# OwlPedal.net
KiCad netlist of a schematic drawn in EAGLE
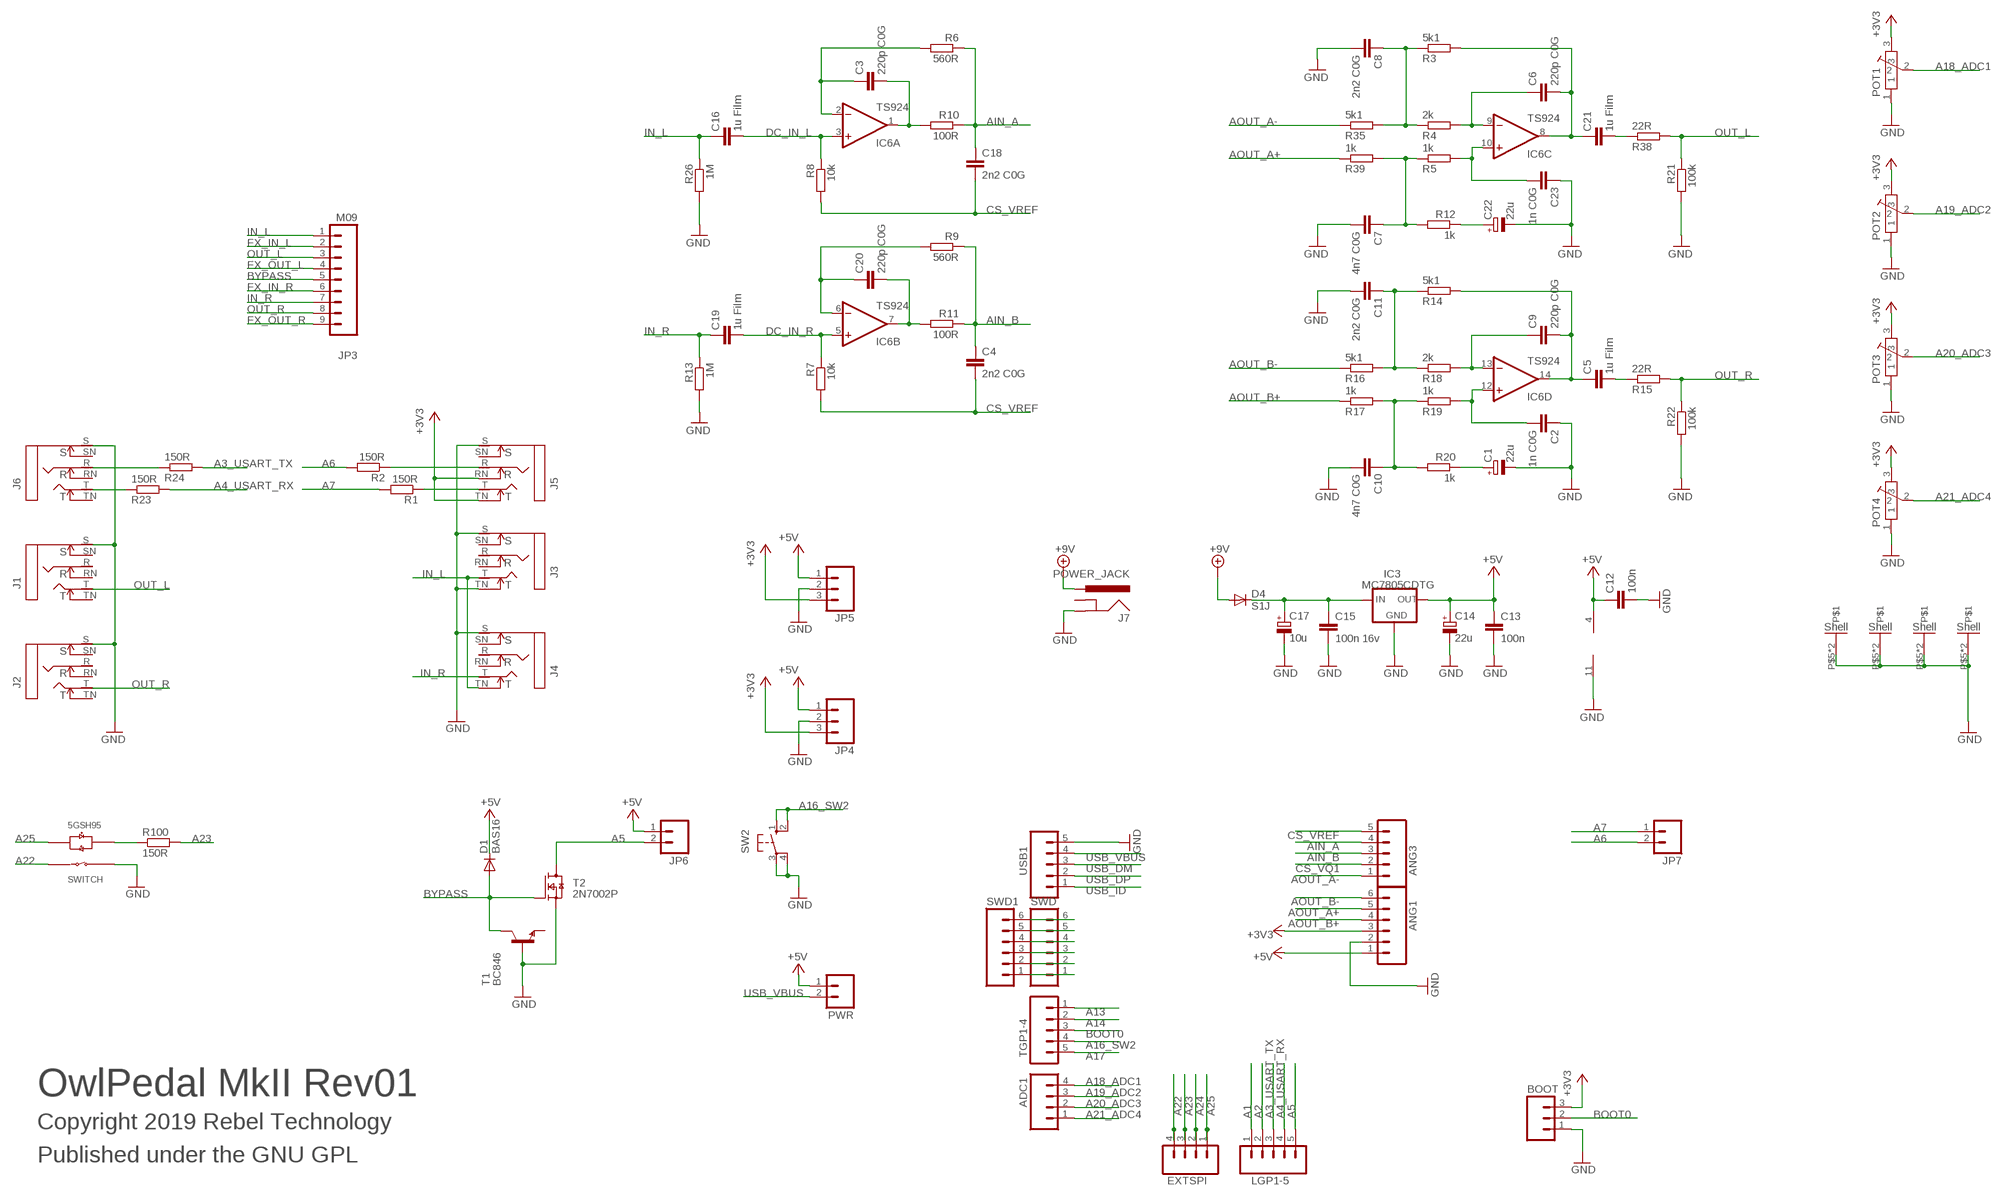
[diagram p0: schematic, sheet 1]

(export (version "E")
  (design (tool "Eeschema 10.0.6"))
  (components
    (comp (ref "ADC1")
      (value "M04PTH")
      (footprint "eagle-import:1X04")
      (libsource (lib "eagle-import") (part "M04PTH"))
    )
    (comp (ref "ANG1")
      (value "M06SIP")
      (footprint "eagle-import:1X06")
      (libsource (lib "eagle-import") (part "M06SIP"))
    )
    (comp (ref "ANG3")
      (value "M05PTH")
      (footprint "eagle-import:1X05")
      (libsource (lib "eagle-import") (part "M05PTH"))
    )
    (comp (ref "BOOT")
      (value "M03PTH")
      (footprint "eagle-import:1X03")
      (libsource (lib "eagle-import") (part "M03PTH"))
    )
    (comp (ref "C1")
      (value "22u")
      (footprint "eagle-import:CPOL-5")
      (libsource (lib "eagle-import") (part "CPOL-EU153CLV-0505"))
    )
    (comp (ref "C2")
      (value "1n C0G")
      (footprint "eagle-import:C0603")
      (libsource (lib "eagle-import") (part "resistor_C-EUC0603"))
    )
    (comp (ref "C3")
      (value "220p C0G")
      (footprint "eagle-import:C0603")
      (libsource (lib "eagle-import") (part "resistor_C-EUC0603"))
    )
    (comp (ref "C4")
      (value "2n2 C0G")
      (footprint "eagle-import:C0603")
      (libsource (lib "eagle-import") (part "resistor_C-EUC0603"))
    )
    (comp (ref "C5")
      (value "1u Film")
      (footprint "eagle-import:C1210")
      (libsource (lib "eagle-import") (part "C-EUC1210"))
    )
    (comp (ref "C6")
      (value "220p C0G")
      (footprint "eagle-import:C0603")
      (libsource (lib "eagle-import") (part "resistor_C-EUC0603"))
    )
    (comp (ref "C7")
      (value "4n7 C0G")
      (footprint "eagle-import:C0603")
      (libsource (lib "eagle-import") (part "resistor_C-EUC0603"))
    )
    (comp (ref "C8")
      (value "2n2 C0G")
      (footprint "eagle-import:C0603")
      (libsource (lib "eagle-import") (part "resistor_C-EUC0603"))
    )
    (comp (ref "C9")
      (value "220p C0G")
      (footprint "eagle-import:C0603")
      (libsource (lib "eagle-import") (part "resistor_C-EUC0603"))
    )
    (comp (ref "C10")
      (value "4n7 C0G")
      (footprint "eagle-import:C0603")
      (libsource (lib "eagle-import") (part "resistor_C-EUC0603"))
    )
    (comp (ref "C11")
      (value "2n2 C0G")
      (footprint "eagle-import:C0603")
      (libsource (lib "eagle-import") (part "resistor_C-EUC0603"))
    )
    (comp (ref "C12")
      (value "100n")
      (footprint "eagle-import:C0603")
      (libsource (lib "eagle-import") (part "resistor_C-EUC0603"))
    )
    (comp (ref "C13")
      (value "100n")
      (footprint "eagle-import:C0603")
      (libsource (lib "eagle-import") (part "C-EUC0603"))
    )
    (comp (ref "C14")
      (value "22u")
      (footprint "eagle-import:CPOL-5")
      (libsource (lib "eagle-import") (part "CPOL-EU153CLV-0505"))
    )
    (comp (ref "C15")
      (value "100n 16v")
      (footprint "eagle-import:C0603")
      (libsource (lib "eagle-import") (part "C-EUC0603"))
    )
    (comp (ref "C16")
      (value "1u Film")
      (footprint "eagle-import:C1210")
      (libsource (lib "eagle-import") (part "C-EUC1210"))
    )
    (comp (ref "C17")
      (value "10u")
      (footprint "eagle-import:CPOL-5")
      (libsource (lib "eagle-import") (part "CPOL-EU153CLV-0505"))
    )
    (comp (ref "C18")
      (value "2n2 C0G")
      (footprint "eagle-import:C0603")
      (libsource (lib "eagle-import") (part "resistor_C-EUC0603"))
    )
    (comp (ref "C19")
      (value "1u Film")
      (footprint "eagle-import:C1210")
      (libsource (lib "eagle-import") (part "C-EUC1210"))
    )
    (comp (ref "C20")
      (value "220p C0G")
      (footprint "eagle-import:C0603")
      (libsource (lib "eagle-import") (part "resistor_C-EUC0603"))
    )
    (comp (ref "C21")
      (value "1u Film")
      (footprint "eagle-import:C1210")
      (libsource (lib "eagle-import") (part "C-EUC1210"))
    )
    (comp (ref "C22")
      (value "22u")
      (footprint "eagle-import:CPOL-5")
      (libsource (lib "eagle-import") (part "CPOL-EU153CLV-0505"))
    )
    (comp (ref "C23")
      (value "1n C0G")
      (footprint "eagle-import:C0603")
      (libsource (lib "eagle-import") (part "resistor_C-EUC0603"))
    )
    (comp (ref "D1")
      (value "BAS16")
      (footprint "eagle-import:SOT23")
      (libsource (lib "eagle-import") (part "BAS16"))
    )
    (comp (ref "D4")
      (value "S1J")
      (footprint "eagle-import:SMA-DIODE")
      (libsource (lib "eagle-import") (part "DIODESMA"))
    )
    (comp (ref "EXTSPI")
      (value "M04PTH")
      (footprint "eagle-import:1X04")
      (libsource (lib "eagle-import") (part "M04PTH"))
    )
    (comp (ref "IC3")
      (value "MC7805CDTG")
      (footprint "eagle-import:DPACK")
      (libsource (lib "eagle-import") (part "MC78XX"))
    )
    (comp (ref "IC6")
      (value "TS924")
      (footprint "eagle-import:SO14")
      (libsource (lib "eagle-import") (part "LM324D"))
    )
    (comp (ref "J1")
      (value "NEUTRIK_NMJ6HCD2")
      (footprint "eagle-import:NMJ6HCD2")
      (libsource (lib "eagle-import") (part "NEUTRIK_NMJ6HCD2"))
    )
    (comp (ref "J2")
      (value "NEUTRIK_NMJ6HCD2")
      (footprint "eagle-import:NMJ6HCD2")
      (libsource (lib "eagle-import") (part "NEUTRIK_NMJ6HCD2"))
    )
    (comp (ref "J3")
      (value "NEUTRIK_NMJ6HCD2")
      (footprint "eagle-import:NMJ6HCD2")
      (libsource (lib "eagle-import") (part "NEUTRIK_NMJ6HCD2"))
    )
    (comp (ref "J4")
      (value "NEUTRIK_NMJ6HCD2")
      (footprint "eagle-import:NMJ6HCD2")
      (libsource (lib "eagle-import") (part "NEUTRIK_NMJ6HCD2"))
    )
    (comp (ref "J5")
      (value "NEUTRIK_NMJ6HCD2")
      (footprint "eagle-import:NMJ6HCD2")
      (libsource (lib "eagle-import") (part "NEUTRIK_NMJ6HCD2"))
    )
    (comp (ref "J6")
      (value "NEUTRIK_NMJ6HCD2")
      (footprint "eagle-import:NMJ6HCD2")
      (libsource (lib "eagle-import") (part "NEUTRIK_NMJ6HCD2"))
    )
    (comp (ref "J7")
      (value "POWER_JACK")
      (footprint "eagle-import:DC_JACK_SLOT")
      (libsource (lib "eagle-import") (part "POWER_JACK"))
    )
    (comp (ref "JP3")
      (value "M09")
      (footprint "eagle-import:1X09")
      (libsource (lib "eagle-import") (part "M09"))
    )
    (comp (ref "JP4")
      (value "M03PTH")
      (footprint "eagle-import:1X03")
      (libsource (lib "eagle-import") (part "M03PTH"))
    )
    (comp (ref "JP5")
      (value "M03PTH")
      (footprint "eagle-import:1X03")
      (libsource (lib "eagle-import") (part "M03PTH"))
    )
    (comp (ref "JP6")
      (value "M02PTH")
      (footprint "eagle-import:1X02")
      (libsource (lib "eagle-import") (part "M02PTH"))
    )
    (comp (ref "JP7")
      (value "M02PTH")
      (footprint "eagle-import:1X02")
      (libsource (lib "eagle-import") (part "M02PTH"))
    )
    (comp (ref "LGP1-5")
      (value "M05PTH")
      (footprint "eagle-import:1X05")
      (libsource (lib "eagle-import") (part "M05PTH"))
    )
    (comp (ref "POT1")
      (value "POT-ALPS-RK09L1140")
      (footprint "eagle-import:POT-ALPS-RK09L1140")
      (libsource (lib "eagle-import") (part "POT-ALPS-RK09L1140"))
    )
    (comp (ref "POT2")
      (value "POT-ALPS-RK09L1140")
      (footprint "eagle-import:POT-ALPS-RK09L1140")
      (libsource (lib "eagle-import") (part "POT-ALPS-RK09L1140"))
    )
    (comp (ref "POT3")
      (value "POT-ALPS-RK09L1140")
      (footprint "eagle-import:POT-ALPS-RK09L1140")
      (libsource (lib "eagle-import") (part "POT-ALPS-RK09L1140"))
    )
    (comp (ref "POT4")
      (value "POT-ALPS-RK09L1140")
      (footprint "eagle-import:POT-ALPS-RK09L1140")
      (libsource (lib "eagle-import") (part "POT-ALPS-RK09L1140"))
    )
    (comp (ref "PWR")
      (value "M02PTH")
      (footprint "eagle-import:1X02")
      (libsource (lib "eagle-import") (part "M02PTH"))
    )
    (comp (ref "R1")
      (value "150R")
      (footprint "eagle-import:0603")
      (libsource (lib "eagle-import") (part "R-EU_0603"))
    )
    (comp (ref "R2")
      (value "150R")
      (footprint "eagle-import:0603")
      (libsource (lib "eagle-import") (part "R-EU_0603"))
    )
    (comp (ref "R3")
      (value "5k1")
      (footprint "eagle-import:0603")
      (libsource (lib "eagle-import") (part "R-EU_0603"))
    )
    (comp (ref "R4")
      (value "2k")
      (footprint "eagle-import:0603")
      (libsource (lib "eagle-import") (part "R-EU_0603"))
    )
    (comp (ref "R5")
      (value "1k")
      (footprint "eagle-import:0603")
      (libsource (lib "eagle-import") (part "R-EU_0603"))
    )
    (comp (ref "R6")
      (value "560R")
      (footprint "eagle-import:0603")
      (libsource (lib "eagle-import") (part "R-EU_0603"))
    )
    (comp (ref "R7")
      (value "10k")
      (footprint "eagle-import:0603")
      (libsource (lib "eagle-import") (part "R-EU_0603"))
    )
    (comp (ref "R8")
      (value "10k")
      (footprint "eagle-import:0603")
      (libsource (lib "eagle-import") (part "R-EU_0603"))
    )
    (comp (ref "R9")
      (value "560R")
      (footprint "eagle-import:0603")
      (libsource (lib "eagle-import") (part "R-EU_0603"))
    )
    (comp (ref "R10")
      (value "100R")
      (footprint "eagle-import:0603")
      (libsource (lib "eagle-import") (part "R-EU_0603"))
    )
    (comp (ref "R11")
      (value "100R")
      (footprint "eagle-import:0603")
      (libsource (lib "eagle-import") (part "R-EU_0603"))
    )
    (comp (ref "R12")
      (value "1k")
      (footprint "eagle-import:0603")
      (libsource (lib "eagle-import") (part "R-EU_0603"))
    )
    (comp (ref "R13")
      (value "1M")
      (footprint "eagle-import:0603")
      (libsource (lib "eagle-import") (part "R-EU_0603"))
    )
    (comp (ref "R14")
      (value "5k1")
      (footprint "eagle-import:0603")
      (libsource (lib "eagle-import") (part "R-EU_0603"))
    )
    (comp (ref "R15")
      (value "22R")
      (footprint "eagle-import:0603")
      (libsource (lib "eagle-import") (part "R-EU_0603"))
    )
    (comp (ref "R16")
      (value "5k1")
      (footprint "eagle-import:0603")
      (libsource (lib "eagle-import") (part "R-EU_0603"))
    )
    (comp (ref "R17")
      (value "1k")
      (footprint "eagle-import:0603")
      (libsource (lib "eagle-import") (part "R-EU_0603"))
    )
    (comp (ref "R18")
      (value "2k")
      (footprint "eagle-import:0603")
      (libsource (lib "eagle-import") (part "R-EU_0603"))
    )
    (comp (ref "R19")
      (value "1k")
      (footprint "eagle-import:0603")
      (libsource (lib "eagle-import") (part "R-EU_0603"))
    )
    (comp (ref "R20")
      (value "1k")
      (footprint "eagle-import:0603")
      (libsource (lib "eagle-import") (part "R-EU_0603"))
    )
    (comp (ref "R21")
      (value "100k")
      (footprint "eagle-import:0603")
      (libsource (lib "eagle-import") (part "R-EU_0603"))
    )
    (comp (ref "R22")
      (value "100k")
      (footprint "eagle-import:0603")
      (libsource (lib "eagle-import") (part "R-EU_0603"))
    )
    (comp (ref "R23")
      (value "150R")
      (footprint "eagle-import:0603")
      (libsource (lib "eagle-import") (part "R-EU_0603"))
    )
    (comp (ref "R24")
      (value "150R")
      (footprint "eagle-import:0603")
      (libsource (lib "eagle-import") (part "R-EU_0603"))
    )
    (comp (ref "R26")
      (value "1M")
      (footprint "eagle-import:0603")
      (libsource (lib "eagle-import") (part "R-EU_0603"))
    )
    (comp (ref "R35")
      (value "5k1")
      (footprint "eagle-import:0603")
      (libsource (lib "eagle-import") (part "R-EU_0603"))
    )
    (comp (ref "R38")
      (value "22R")
      (footprint "eagle-import:0603")
      (libsource (lib "eagle-import") (part "R-EU_0603"))
    )
    (comp (ref "R39")
      (value "1k")
      (footprint "eagle-import:0603")
      (libsource (lib "eagle-import") (part "R-EU_0603"))
    )
    (comp (ref "R100")
      (value "150R")
      (footprint "eagle-import:0603")
      (libsource (lib "eagle-import") (part "R-EU_0603"))
    )
    (comp (ref "SW2")
      (value "10-XX")
      (footprint "eagle-import:B3F-10XX")
      (fields (field (name "MPN") "B3F-1000"))
      (libsource (lib "eagle-import") (part "10-XX"))
    )
    (comp (ref "SWD")
      (value "M06SIP")
      (footprint "eagle-import:1X06")
      (libsource (lib "eagle-import") (part "M06SIP"))
    )
    (comp (ref "SWD1")
      (value "M06SIP")
      (footprint "eagle-import:1X06")
      (libsource (lib "eagle-import") (part "M06SIP"))
    )
    (comp (ref "T1")
      (value "BC846")
      (footprint "eagle-import:SOT23")
      (libsource (lib "eagle-import") (part "BC846"))
    )
    (comp (ref "T2")
      (value "2N7002P")
      (footprint "eagle-import:SOT23")
      (libsource (lib "eagle-import") (part "2N7002P"))
    )
    (comp (ref "TGP1-4")
      (value "M05PTH")
      (footprint "eagle-import:1X05")
      (libsource (lib "eagle-import") (part "M05PTH"))
    )
    (comp (ref "U$1")
      (value "5GTH9")
      (footprint "eagle-import:5GTH9")
      (libsource (lib "eagle-import") (part "5GTH9"))
    )
    (comp (ref "USB1")
      (value "M05PTH")
      (footprint "eagle-import:1X05")
      (libsource (lib "eagle-import") (part "M05PTH"))
    )
  )
  (nets
    (net (code "1") (name "+3V3") (class "Default")
      (node (ref "ANG1") (pin "3") (pinfunction "3_3") (pintype "passive"))
      (node (ref "BOOT") (pin "3") (pinfunction "3_3") (pintype "passive"))
      (node (ref "J5") (pin "RN") (pinfunction "RN_RN") (pintype "passive"))
      (node (ref "J5") (pin "TN") (pinfunction "TN_TN") (pintype "passive"))
      (node (ref "JP4") (pin "3") (pinfunction "3_3") (pintype "passive"))
      (node (ref "JP5") (pin "3") (pinfunction "3_3") (pintype "passive"))
      (node (ref "POT1") (pin "3") (pinfunction "3_3") (pintype "bidirectional"))
      (node (ref "POT2") (pin "3") (pinfunction "3_3") (pintype "bidirectional"))
      (node (ref "POT3") (pin "3") (pinfunction "3_3") (pintype "bidirectional"))
      (node (ref "POT4") (pin "3") (pinfunction "3_3") (pintype "bidirectional"))
    )
    (net (code "2") (name "+5V") (class "Default")
      (node (ref "ANG1") (pin "1") (pinfunction "1_1") (pintype "passive"))
      (node (ref "C12") (pin "1") (pinfunction "1_1") (pintype "passive"))
      (node (ref "C13") (pin "1") (pinfunction "1_1") (pintype "passive"))
      (node (ref "C14") (pin "+") (pinfunction "+_+") (pintype "passive"))
      (node (ref "D1") (pin "3") (pinfunction "K_3") (pintype "passive"))
      (node (ref "IC3") (pin "3") (pinfunction "OUT_3") (pintype "passive"))
      (node (ref "IC6") (pin "4") (pinfunction "V+_4") (pintype "power_in"))
      (node (ref "JP4") (pin "1") (pinfunction "1_1") (pintype "passive"))
      (node (ref "JP5") (pin "1") (pinfunction "1_1") (pintype "passive"))
      (node (ref "JP6") (pin "1") (pinfunction "1_1") (pintype "passive"))
      (node (ref "PWR") (pin "1") (pinfunction "1_1") (pintype "passive"))
    )
    (net (code "3") (name "+9V") (class "Default")
      (node (ref "D4") (pin "A") (pinfunction "A_A") (pintype "passive"))
      (node (ref "J7") (pin "PWR") (pinfunction "PWR_PWR") (pintype "bidirectional"))
    )
    (net (code "4") (name "/A1") (class "Default")
      (node (ref "LGP1-5") (pin "1") (pinfunction "1_1") (pintype "passive"))
    )
    (net (code "5") (name "/A2") (class "Default")
      (node (ref "LGP1-5") (pin "2") (pinfunction "2_2") (pintype "passive"))
    )
    (net (code "6") (name "/A3_USART_TX") (class "Default")
      (node (ref "LGP1-5") (pin "3") (pinfunction "3_3") (pintype "passive"))
      (node (ref "R24") (pin "2") (pinfunction "2_2") (pintype "passive"))
    )
    (net (code "7") (name "/A4_USART_RX") (class "Default")
      (node (ref "LGP1-5") (pin "4") (pinfunction "4_4") (pintype "passive"))
      (node (ref "R23") (pin "2") (pinfunction "2_2") (pintype "passive"))
    )
    (net (code "8") (name "/A5") (class "Default")
      (node (ref "JP6") (pin "2") (pinfunction "2_2") (pintype "passive"))
      (node (ref "LGP1-5") (pin "5") (pinfunction "5_5") (pintype "passive"))
      (node (ref "T2") (pin "3") (pinfunction "D_3") (pintype "passive"))
    )
    (net (code "9") (name "/A6") (class "Default")
      (node (ref "JP7") (pin "2") (pinfunction "2_2") (pintype "passive"))
      (node (ref "R2") (pin "2") (pinfunction "2_2") (pintype "passive"))
    )
    (net (code "10") (name "/A7") (class "Default")
      (node (ref "JP7") (pin "1") (pinfunction "1_1") (pintype "passive"))
      (node (ref "R1") (pin "2") (pinfunction "2_2") (pintype "passive"))
    )
    (net (code "11") (name "/A13") (class "Default")
      (node (ref "TGP1-4") (pin "1") (pinfunction "1_1") (pintype "passive"))
    )
    (net (code "12") (name "/A14") (class "Default")
      (node (ref "TGP1-4") (pin "2") (pinfunction "2_2") (pintype "passive"))
    )
    (net (code "13") (name "/A16_SW2") (class "Default")
      (node (ref "SW2") (pin "1") (pinfunction "S_1") (pintype "passive"))
      (node (ref "SW2") (pin "2") (pinfunction "S1_2") (pintype "passive"))
      (node (ref "TGP1-4") (pin "4") (pinfunction "4_4") (pintype "passive"))
    )
    (net (code "14") (name "/A17") (class "Default")
      (node (ref "TGP1-4") (pin "5") (pinfunction "5_5") (pintype "passive"))
    )
    (net (code "15") (name "/A18_ADC1") (class "Default")
      (node (ref "ADC1") (pin "4") (pinfunction "4_4") (pintype "passive"))
      (node (ref "POT1") (pin "2") (pinfunction "2_2") (pintype "bidirectional"))
    )
    (net (code "16") (name "/A19_ADC2") (class "Default")
      (node (ref "ADC1") (pin "3") (pinfunction "3_3") (pintype "passive"))
      (node (ref "POT2") (pin "2") (pinfunction "2_2") (pintype "bidirectional"))
    )
    (net (code "17") (name "/A20_ADC3") (class "Default")
      (node (ref "ADC1") (pin "2") (pinfunction "2_2") (pintype "passive"))
      (node (ref "POT3") (pin "2") (pinfunction "2_2") (pintype "bidirectional"))
    )
    (net (code "18") (name "/A21_ADC4") (class "Default")
      (node (ref "ADC1") (pin "1") (pinfunction "1_1") (pintype "passive"))
      (node (ref "POT4") (pin "2") (pinfunction "2_2") (pintype "bidirectional"))
    )
    (net (code "19") (name "/A22") (class "Default")
      (node (ref "EXTSPI") (pin "4") (pinfunction "4_4") (pintype "passive"))
      (node (ref "U$1") (pin "4") (pinfunction "SWITCH_A_4") (pintype "power_in"))
    )
    (net (code "20") (name "/A23") (class "Default")
      (node (ref "EXTSPI") (pin "3") (pinfunction "3_3") (pintype "passive"))
      (node (ref "R100") (pin "2") (pinfunction "2_2") (pintype "passive"))
    )
    (net (code "21") (name "/A24") (class "Default")
      (node (ref "EXTSPI") (pin "2") (pinfunction "2_2") (pintype "passive"))
    )
    (net (code "22") (name "/A25") (class "Default")
      (node (ref "EXTSPI") (pin "1") (pinfunction "1_1") (pintype "passive"))
      (node (ref "U$1") (pin "-2") (pinfunction "LED_G+_-2") (pintype "input"))
    )
    (net (code "23") (name "/AIN_A") (class "Default")
      (node (ref "ANG3") (pin "4") (pinfunction "4_4") (pintype "passive"))
      (node (ref "C18") (pin "1") (pinfunction "1_1") (pintype "passive"))
      (node (ref "R10") (pin "1") (pinfunction "1_1") (pintype "passive"))
      (node (ref "R6") (pin "1") (pinfunction "1_1") (pintype "passive"))
    )
    (net (code "24") (name "/AIN_B") (class "Default")
      (node (ref "ANG3") (pin "3") (pinfunction "3_3") (pintype "passive"))
      (node (ref "C4") (pin "1") (pinfunction "1_1") (pintype "passive"))
      (node (ref "R11") (pin "1") (pinfunction "1_1") (pintype "passive"))
      (node (ref "R9") (pin "1") (pinfunction "1_1") (pintype "passive"))
    )
    (net (code "25") (name "/AOUT_A+") (class "Default")
      (node (ref "ANG1") (pin "5") (pinfunction "5_5") (pintype "passive"))
      (node (ref "R39") (pin "1") (pinfunction "1_1") (pintype "passive"))
    )
    (net (code "26") (name "/AOUT_A-") (class "Default")
      (node (ref "ANG3") (pin "1") (pinfunction "1_1") (pintype "passive"))
      (node (ref "R35") (pin "1") (pinfunction "1_1") (pintype "passive"))
    )
    (net (code "27") (name "/AOUT_B+") (class "Default")
      (node (ref "ANG1") (pin "4") (pinfunction "4_4") (pintype "passive"))
      (node (ref "R17") (pin "1") (pinfunction "1_1") (pintype "passive"))
    )
    (net (code "28") (name "/AOUT_B-") (class "Default")
      (node (ref "ANG1") (pin "6") (pinfunction "6_6") (pintype "passive"))
      (node (ref "R16") (pin "1") (pinfunction "1_1") (pintype "passive"))
    )
    (net (code "29") (name "/BOOT0") (class "Default")
      (node (ref "BOOT") (pin "2") (pinfunction "2_2") (pintype "passive"))
      (node (ref "TGP1-4") (pin "3") (pinfunction "3_3") (pintype "passive"))
    )
    (net (code "30") (name "/BYPASS") (class "Default")
      (node (ref "D1") (pin "1") (pinfunction "A_1") (pintype "passive"))
      (node (ref "JP3") (pin "5") (pinfunction "5_5") (pintype "passive"))
      (node (ref "T1") (pin "3") (pinfunction "C_3") (pintype "passive"))
      (node (ref "T2") (pin "1") (pinfunction "G_1") (pintype "passive"))
    )
    (net (code "31") (name "/CS_VQ1") (class "Default")
      (node (ref "ANG3") (pin "2") (pinfunction "2_2") (pintype "passive"))
    )
    (net (code "32") (name "/CS_VREF") (class "Default")
      (node (ref "ANG3") (pin "5") (pinfunction "5_5") (pintype "passive"))
      (node (ref "C18") (pin "2") (pinfunction "2_2") (pintype "passive"))
      (node (ref "C4") (pin "2") (pinfunction "2_2") (pintype "passive"))
      (node (ref "R7") (pin "2") (pinfunction "2_2") (pintype "passive"))
      (node (ref "R8") (pin "2") (pinfunction "2_2") (pintype "passive"))
    )
    (net (code "33") (name "/DC_IN_L") (class "Default")
      (node (ref "C16") (pin "1") (pinfunction "1_1") (pintype "passive"))
      (node (ref "IC6") (pin "3") (pinfunction "+IN_3") (pintype "input"))
      (node (ref "R8") (pin "1") (pinfunction "1_1") (pintype "passive"))
    )
    (net (code "34") (name "/DC_IN_R") (class "Default")
      (node (ref "C19") (pin "1") (pinfunction "1_1") (pintype "passive"))
      (node (ref "IC6") (pin "5") (pinfunction "+IN_5") (pintype "input"))
      (node (ref "R7") (pin "1") (pinfunction "1_1") (pintype "passive"))
    )
    (net (code "35") (name "/FX_IN_L") (class "Default")
      (node (ref "JP3") (pin "2") (pinfunction "2_2") (pintype "passive"))
    )
    (net (code "36") (name "/FX_IN_R") (class "Default")
      (node (ref "JP3") (pin "6") (pinfunction "6_6") (pintype "passive"))
    )
    (net (code "37") (name "/FX_OUT_L") (class "Default")
      (node (ref "JP3") (pin "4") (pinfunction "4_4") (pintype "passive"))
    )
    (net (code "38") (name "/FX_OUT_R") (class "Default")
      (node (ref "JP3") (pin "9") (pinfunction "9_9") (pintype "passive"))
    )
    (net (code "39") (name "/IN_L") (class "Default")
      (node (ref "C16") (pin "2") (pinfunction "2_2") (pintype "passive"))
      (node (ref "J3") (pin "T") (pinfunction "T_T") (pintype "passive"))
      (node (ref "J4") (pin "TN") (pinfunction "TN_TN") (pintype "passive"))
      (node (ref "JP3") (pin "1") (pinfunction "1_1") (pintype "passive"))
      (node (ref "R26") (pin "1") (pinfunction "1_1") (pintype "passive"))
    )
    (net (code "40") (name "/IN_R") (class "Default")
      (node (ref "C19") (pin "2") (pinfunction "2_2") (pintype "passive"))
      (node (ref "J4") (pin "T") (pinfunction "T_T") (pintype "passive"))
      (node (ref "JP3") (pin "7") (pinfunction "7_7") (pintype "passive"))
      (node (ref "R13") (pin "1") (pinfunction "1_1") (pintype "passive"))
    )
    (net (code "41") (name "/OUT_L") (class "Default")
      (node (ref "J1") (pin "T") (pinfunction "T_T") (pintype "passive"))
      (node (ref "JP3") (pin "3") (pinfunction "3_3") (pintype "passive"))
      (node (ref "R21") (pin "1") (pinfunction "1_1") (pintype "passive"))
      (node (ref "R38") (pin "2") (pinfunction "2_2") (pintype "passive"))
    )
    (net (code "42") (name "/OUT_R") (class "Default")
      (node (ref "J2") (pin "T") (pinfunction "T_T") (pintype "passive"))
      (node (ref "JP3") (pin "8") (pinfunction "8_8") (pintype "passive"))
      (node (ref "R15") (pin "2") (pinfunction "2_2") (pintype "passive"))
      (node (ref "R22") (pin "1") (pinfunction "1_1") (pintype "passive"))
    )
    (net (code "43") (name "/USB_DM") (class "Default")
      (node (ref "USB1") (pin "3") (pinfunction "3_3") (pintype "passive"))
    )
    (net (code "44") (name "/USB_DP") (class "Default")
      (node (ref "USB1") (pin "2") (pinfunction "2_2") (pintype "passive"))
    )
    (net (code "45") (name "/USB_ID") (class "Default")
      (node (ref "USB1") (pin "1") (pinfunction "1_1") (pintype "passive"))
    )
    (net (code "46") (name "/USB_VBUS") (class "Default")
      (node (ref "PWR") (pin "2") (pinfunction "2_2") (pintype "passive"))
      (node (ref "USB1") (pin "4") (pinfunction "4_4") (pintype "passive"))
    )
    (net (code "47") (name "GND") (class "Default")
      (node (ref "ANG1") (pin "2") (pinfunction "2_2") (pintype "passive"))
      (node (ref "BOOT") (pin "1") (pinfunction "1_1") (pintype "passive"))
      (node (ref "C1") (pin "-") (pinfunction "-_-") (pintype "passive"))
      (node (ref "C10") (pin "2") (pinfunction "2_2") (pintype "passive"))
      (node (ref "C11") (pin "2") (pinfunction "2_2") (pintype "passive"))
      (node (ref "C12") (pin "2") (pinfunction "2_2") (pintype "passive"))
      (node (ref "C13") (pin "2") (pinfunction "2_2") (pintype "passive"))
      (node (ref "C14") (pin "-") (pinfunction "-_-") (pintype "passive"))
      (node (ref "C15") (pin "2") (pinfunction "2_2") (pintype "passive"))
      (node (ref "C17") (pin "-") (pinfunction "-_-") (pintype "passive"))
      (node (ref "C2") (pin "1") (pinfunction "1_1") (pintype "passive"))
      (node (ref "C22") (pin "-") (pinfunction "-_-") (pintype "passive"))
      (node (ref "C23") (pin "1") (pinfunction "1_1") (pintype "passive"))
      (node (ref "C7") (pin "2") (pinfunction "2_2") (pintype "passive"))
      (node (ref "C8") (pin "2") (pinfunction "2_2") (pintype "passive"))
      (node (ref "IC3") (pin "4") (pinfunction "GND_4") (pintype "input"))
      (node (ref "IC6") (pin "11") (pinfunction "V-_11") (pintype "power_in"))
      (node (ref "J1") (pin "S") (pinfunction "S_S") (pintype "passive"))
      (node (ref "J2") (pin "S") (pinfunction "S_S") (pintype "passive"))
      (node (ref "J3") (pin "S") (pinfunction "S_S") (pintype "passive"))
      (node (ref "J3") (pin "TN") (pinfunction "TN_TN") (pintype "passive"))
      (node (ref "J4") (pin "S") (pinfunction "S_S") (pintype "passive"))
      (node (ref "J5") (pin "S") (pinfunction "S_S") (pintype "passive"))
      (node (ref "J6") (pin "S") (pinfunction "S_S") (pintype "passive"))
      (node (ref "J7") (pin "GND") (pinfunction "GND_GND") (pintype "bidirectional"))
      (node (ref "JP4") (pin "2") (pinfunction "2_2") (pintype "passive"))
      (node (ref "JP5") (pin "2") (pinfunction "2_2") (pintype "passive"))
      (node (ref "POT1") (pin "1") (pinfunction "1_1") (pintype "bidirectional"))
      (node (ref "POT1") (pin "P$5") (pinfunction "P$1_P$5") (pintype "bidirectional"))
      (node (ref "POT1") (pin "P$6") (pinfunction "P$1_P$6") (pintype "bidirectional"))
      (node (ref "POT2") (pin "1") (pinfunction "1_1") (pintype "bidirectional"))
      (node (ref "POT2") (pin "P$5") (pinfunction "P$1_P$5") (pintype "bidirectional"))
      (node (ref "POT2") (pin "P$6") (pinfunction "P$1_P$6") (pintype "bidirectional"))
      (node (ref "POT3") (pin "1") (pinfunction "1_1") (pintype "bidirectional"))
      (node (ref "POT3") (pin "P$5") (pinfunction "P$1_P$5") (pintype "bidirectional"))
      (node (ref "POT3") (pin "P$6") (pinfunction "P$1_P$6") (pintype "bidirectional"))
      (node (ref "POT4") (pin "1") (pinfunction "1_1") (pintype "bidirectional"))
      (node (ref "POT4") (pin "P$5") (pinfunction "P$1_P$5") (pintype "bidirectional"))
      (node (ref "POT4") (pin "P$6") (pinfunction "P$1_P$6") (pintype "bidirectional"))
      (node (ref "R13") (pin "2") (pinfunction "2_2") (pintype "passive"))
      (node (ref "R21") (pin "2") (pinfunction "2_2") (pintype "passive"))
      (node (ref "R22") (pin "2") (pinfunction "2_2") (pintype "passive"))
      (node (ref "R26") (pin "2") (pinfunction "2_2") (pintype "passive"))
      (node (ref "SW2") (pin "3") (pinfunction "P_3") (pintype "passive"))
      (node (ref "SW2") (pin "4") (pinfunction "P1_4") (pintype "passive"))
      (node (ref "T1") (pin "1") (pinfunction "B_1") (pintype "passive"))
      (node (ref "T2") (pin "2") (pinfunction "S_2") (pintype "passive"))
      (node (ref "U$1") (pin "1") (pinfunction "SWITCH_B_1") (pintype "power_in"))
      (node (ref "USB1") (pin "5") (pinfunction "5_5") (pintype "passive"))
    )
    (net (code "48") (name "Net-(C1-Pad+)") (class "Default")
      (node (ref "C1") (pin "+") (pinfunction "+_+") (pintype "passive"))
      (node (ref "R20") (pin "1") (pinfunction "1_1") (pintype "passive"))
    )
    (net (code "49") (name "Net-(C5-Pad2)") (class "Default")
      (node (ref "C5") (pin "2") (pinfunction "2_2") (pintype "passive"))
      (node (ref "R15") (pin "1") (pinfunction "1_1") (pintype "passive"))
    )
    (net (code "50") (name "Net-(C7-Pad1)") (class "Default")
      (node (ref "C7") (pin "1") (pinfunction "1_1") (pintype "passive"))
      (node (ref "R12") (pin "2") (pinfunction "2_2") (pintype "passive"))
      (node (ref "R39") (pin "2") (pinfunction "2_2") (pintype "passive"))
      (node (ref "R5") (pin "1") (pinfunction "1_1") (pintype "passive"))
    )
    (net (code "51") (name "Net-(C8-Pad1)") (class "Default")
      (node (ref "C8") (pin "1") (pinfunction "1_1") (pintype "passive"))
      (node (ref "R3") (pin "1") (pinfunction "1_1") (pintype "passive"))
      (node (ref "R35") (pin "2") (pinfunction "2_2") (pintype "passive"))
      (node (ref "R4") (pin "1") (pinfunction "1_1") (pintype "passive"))
    )
    (net (code "52") (name "Net-(C10-Pad1)") (class "Default")
      (node (ref "C10") (pin "1") (pinfunction "1_1") (pintype "passive"))
      (node (ref "R17") (pin "2") (pinfunction "2_2") (pintype "passive"))
      (node (ref "R19") (pin "1") (pinfunction "1_1") (pintype "passive"))
      (node (ref "R20") (pin "2") (pinfunction "2_2") (pintype "passive"))
    )
    (net (code "53") (name "Net-(C11-Pad1)") (class "Default")
      (node (ref "C11") (pin "1") (pinfunction "1_1") (pintype "passive"))
      (node (ref "R14") (pin "1") (pinfunction "1_1") (pintype "passive"))
      (node (ref "R16") (pin "2") (pinfunction "2_2") (pintype "passive"))
      (node (ref "R18") (pin "1") (pinfunction "1_1") (pintype "passive"))
    )
    (net (code "54") (name "Net-(C21-Pad2)") (class "Default")
      (node (ref "C21") (pin "2") (pinfunction "2_2") (pintype "passive"))
      (node (ref "R38") (pin "1") (pinfunction "1_1") (pintype "passive"))
    )
    (net (code "55") (name "Net-(C22-Pad+)") (class "Default")
      (node (ref "C22") (pin "+") (pinfunction "+_+") (pintype "passive"))
      (node (ref "R12") (pin "1") (pinfunction "1_1") (pintype "passive"))
    )
    (net (code "56") (name "Net-(IC3-IN)") (class "Default")
      (node (ref "C15") (pin "1") (pinfunction "1_1") (pintype "passive"))
      (node (ref "C17") (pin "+") (pinfunction "+_+") (pintype "passive"))
      (node (ref "D4") (pin "C") (pinfunction "C_C") (pintype "passive"))
      (node (ref "IC3") (pin "1") (pinfunction "IN_1") (pintype "input"))
    )
    (net (code "57") (name "Net-(IC6A--IN)") (class "Default")
      (node (ref "C3") (pin "1") (pinfunction "1_1") (pintype "passive"))
      (node (ref "IC6") (pin "2") (pinfunction "-IN_2") (pintype "input"))
      (node (ref "R6") (pin "2") (pinfunction "2_2") (pintype "passive"))
    )
    (net (code "58") (name "Net-(IC6A-OUT)") (class "Default")
      (node (ref "C3") (pin "2") (pinfunction "2_2") (pintype "passive"))
      (node (ref "IC6") (pin "1") (pinfunction "OUT_1") (pintype "output"))
      (node (ref "R10") (pin "2") (pinfunction "2_2") (pintype "passive"))
    )
    (net (code "59") (name "Net-(IC6B--IN)") (class "Default")
      (node (ref "C20") (pin "1") (pinfunction "1_1") (pintype "passive"))
      (node (ref "IC6") (pin "6") (pinfunction "-IN_6") (pintype "input"))
      (node (ref "R9") (pin "2") (pinfunction "2_2") (pintype "passive"))
    )
    (net (code "60") (name "Net-(IC6B-OUT)") (class "Default")
      (node (ref "C20") (pin "2") (pinfunction "2_2") (pintype "passive"))
      (node (ref "IC6") (pin "7") (pinfunction "OUT_7") (pintype "output"))
      (node (ref "R11") (pin "2") (pinfunction "2_2") (pintype "passive"))
    )
    (net (code "61") (name "Net-(IC6C-+IN)") (class "Default")
      (node (ref "C23") (pin "2") (pinfunction "2_2") (pintype "passive"))
      (node (ref "IC6") (pin "10") (pinfunction "+IN_10") (pintype "input"))
      (node (ref "R5") (pin "2") (pinfunction "2_2") (pintype "passive"))
    )
    (net (code "62") (name "Net-(IC6C--IN)") (class "Default")
      (node (ref "C6") (pin "1") (pinfunction "1_1") (pintype "passive"))
      (node (ref "IC6") (pin "9") (pinfunction "-IN_9") (pintype "input"))
      (node (ref "R4") (pin "2") (pinfunction "2_2") (pintype "passive"))
    )
    (net (code "63") (name "Net-(IC6C-OUT)") (class "Default")
      (node (ref "C21") (pin "1") (pinfunction "1_1") (pintype "passive"))
      (node (ref "C6") (pin "2") (pinfunction "2_2") (pintype "passive"))
      (node (ref "IC6") (pin "8") (pinfunction "OUT_8") (pintype "output"))
      (node (ref "R3") (pin "2") (pinfunction "2_2") (pintype "passive"))
    )
    (net (code "64") (name "Net-(IC6D-+IN)") (class "Default")
      (node (ref "C2") (pin "2") (pinfunction "2_2") (pintype "passive"))
      (node (ref "IC6") (pin "12") (pinfunction "+IN_12") (pintype "input"))
      (node (ref "R19") (pin "2") (pinfunction "2_2") (pintype "passive"))
    )
    (net (code "65") (name "Net-(IC6D--IN)") (class "Default")
      (node (ref "C9") (pin "1") (pinfunction "1_1") (pintype "passive"))
      (node (ref "IC6") (pin "13") (pinfunction "-IN_13") (pintype "input"))
      (node (ref "R18") (pin "2") (pinfunction "2_2") (pintype "passive"))
    )
    (net (code "66") (name "Net-(IC6D-OUT)") (class "Default")
      (node (ref "C5") (pin "1") (pinfunction "1_1") (pintype "passive"))
      (node (ref "C9") (pin "2") (pinfunction "2_2") (pintype "passive"))
      (node (ref "IC6") (pin "14") (pinfunction "OUT_14") (pintype "output"))
      (node (ref "R14") (pin "2") (pinfunction "2_2") (pintype "passive"))
    )
    (net (code "67") (name "Net-(J5-PadR)") (class "Default")
      (node (ref "J5") (pin "R") (pinfunction "R_R") (pintype "passive"))
      (node (ref "R2") (pin "1") (pinfunction "1_1") (pintype "passive"))
    )
    (net (code "68") (name "Net-(J5-PadT)") (class "Default")
      (node (ref "J5") (pin "T") (pinfunction "T_T") (pintype "passive"))
      (node (ref "R1") (pin "1") (pinfunction "1_1") (pintype "passive"))
    )
    (net (code "69") (name "Net-(J6-PadR)") (class "Default")
      (node (ref "J6") (pin "R") (pinfunction "R_R") (pintype "passive"))
      (node (ref "R24") (pin "1") (pinfunction "1_1") (pintype "passive"))
    )
    (net (code "70") (name "Net-(J6-PadT)") (class "Default")
      (node (ref "J6") (pin "T") (pinfunction "T_T") (pintype "passive"))
      (node (ref "R23") (pin "1") (pinfunction "1_1") (pintype "passive"))
    )
    (net (code "71") (name "Net-(SWD-Pad1)") (class "Default")
      (node (ref "SWD") (pin "1") (pinfunction "1_1") (pintype "passive"))
      (node (ref "SWD1") (pin "1") (pinfunction "1_1") (pintype "passive"))
    )
    (net (code "72") (name "Net-(SWD-Pad2)") (class "Default")
      (node (ref "SWD") (pin "2") (pinfunction "2_2") (pintype "passive"))
      (node (ref "SWD1") (pin "2") (pinfunction "2_2") (pintype "passive"))
    )
    (net (code "73") (name "Net-(SWD-Pad3)") (class "Default")
      (node (ref "SWD") (pin "3") (pinfunction "3_3") (pintype "passive"))
      (node (ref "SWD1") (pin "3") (pinfunction "3_3") (pintype "passive"))
    )
    (net (code "74") (name "Net-(SWD-Pad4)") (class "Default")
      (node (ref "SWD") (pin "4") (pinfunction "4_4") (pintype "passive"))
      (node (ref "SWD1") (pin "4") (pinfunction "4_4") (pintype "passive"))
    )
    (net (code "75") (name "Net-(SWD-Pad5)") (class "Default")
      (node (ref "SWD") (pin "5") (pinfunction "5_5") (pintype "passive"))
      (node (ref "SWD1") (pin "5") (pinfunction "5_5") (pintype "passive"))
    )
    (net (code "76") (name "Net-(SWD-Pad6)") (class "Default")
      (node (ref "SWD") (pin "6") (pinfunction "6_6") (pintype "passive"))
      (node (ref "SWD1") (pin "6") (pinfunction "6_6") (pintype "passive"))
    )
    (net (code "77") (name "Net-(U$1-LED_R+)") (class "Default")
      (node (ref "R100") (pin "1") (pinfunction "1_1") (pintype "passive"))
      (node (ref "U$1") (pin "+3") (pinfunction "LED_R+_+3") (pintype "input"))
    )
    (net (code "78") (name "unconnected-(J1-PadR)") (class "Default")
      (node (ref "J1") (pin "R") (pinfunction "R_R") (pintype "passive"))
    )
    (net (code "79") (name "unconnected-(J1-PadRN)") (class "Default")
      (node (ref "J1") (pin "RN") (pinfunction "RN_RN") (pintype "passive"))
    )
    (net (code "80") (name "unconnected-(J1-PadSN)") (class "Default")
      (node (ref "J1") (pin "SN") (pinfunction "SN_SN") (pintype "passive"))
    )
    (net (code "81") (name "unconnected-(J1-PadTN)") (class "Default")
      (node (ref "J1") (pin "TN") (pinfunction "TN_TN") (pintype "passive"))
    )
    (net (code "82") (name "unconnected-(J2-PadR)") (class "Default")
      (node (ref "J2") (pin "R") (pinfunction "R_R") (pintype "passive"))
    )
    (net (code "83") (name "unconnected-(J2-PadRN)") (class "Default")
      (node (ref "J2") (pin "RN") (pinfunction "RN_RN") (pintype "passive"))
    )
    (net (code "84") (name "unconnected-(J2-PadSN)") (class "Default")
      (node (ref "J2") (pin "SN") (pinfunction "SN_SN") (pintype "passive"))
    )
    (net (code "85") (name "unconnected-(J2-PadTN)") (class "Default")
      (node (ref "J2") (pin "TN") (pinfunction "TN_TN") (pintype "passive"))
    )
    (net (code "86") (name "unconnected-(J3-PadR)") (class "Default")
      (node (ref "J3") (pin "R") (pinfunction "R_R") (pintype "passive"))
    )
    (net (code "87") (name "unconnected-(J3-PadRN)") (class "Default")
      (node (ref "J3") (pin "RN") (pinfunction "RN_RN") (pintype "passive"))
    )
    (net (code "88") (name "unconnected-(J3-PadSN)") (class "Default")
      (node (ref "J3") (pin "SN") (pinfunction "SN_SN") (pintype "passive"))
    )
    (net (code "89") (name "unconnected-(J4-PadR)") (class "Default")
      (node (ref "J4") (pin "R") (pinfunction "R_R") (pintype "passive"))
    )
    (net (code "90") (name "unconnected-(J4-PadRN)") (class "Default")
      (node (ref "J4") (pin "RN") (pinfunction "RN_RN") (pintype "passive"))
    )
    (net (code "91") (name "unconnected-(J4-PadSN)") (class "Default")
      (node (ref "J4") (pin "SN") (pinfunction "SN_SN") (pintype "passive"))
    )
    (net (code "92") (name "unconnected-(J5-PadSN)") (class "Default")
      (node (ref "J5") (pin "SN") (pinfunction "SN_SN") (pintype "passive"))
    )
    (net (code "93") (name "unconnected-(J6-PadRN)") (class "Default")
      (node (ref "J6") (pin "RN") (pinfunction "RN_RN") (pintype "passive"))
    )
    (net (code "94") (name "unconnected-(J6-PadSN)") (class "Default")
      (node (ref "J6") (pin "SN") (pinfunction "SN_SN") (pintype "passive"))
    )
    (net (code "95") (name "unconnected-(J6-PadTN)") (class "Default")
      (node (ref "J6") (pin "TN") (pinfunction "TN_TN") (pintype "passive"))
    )
    (net (code "96") (name "unconnected-(J7-PadGNDBREAK)") (class "Default")
      (node (ref "J7") (pin "GNDBREAK") (pinfunction "GNDBREAK_GNDBREAK") (pintype "bidirectional"))
    )
    (net (code "97") (name "unconnected-(T1-E-Pad2)") (class "Default")
      (node (ref "T1") (pin "2") (pinfunction "E_2") (pintype "passive"))
    )
  )
)
